# opi_link_X_standard.net
KiCad netlist of a schematic drawn in Altium Designer
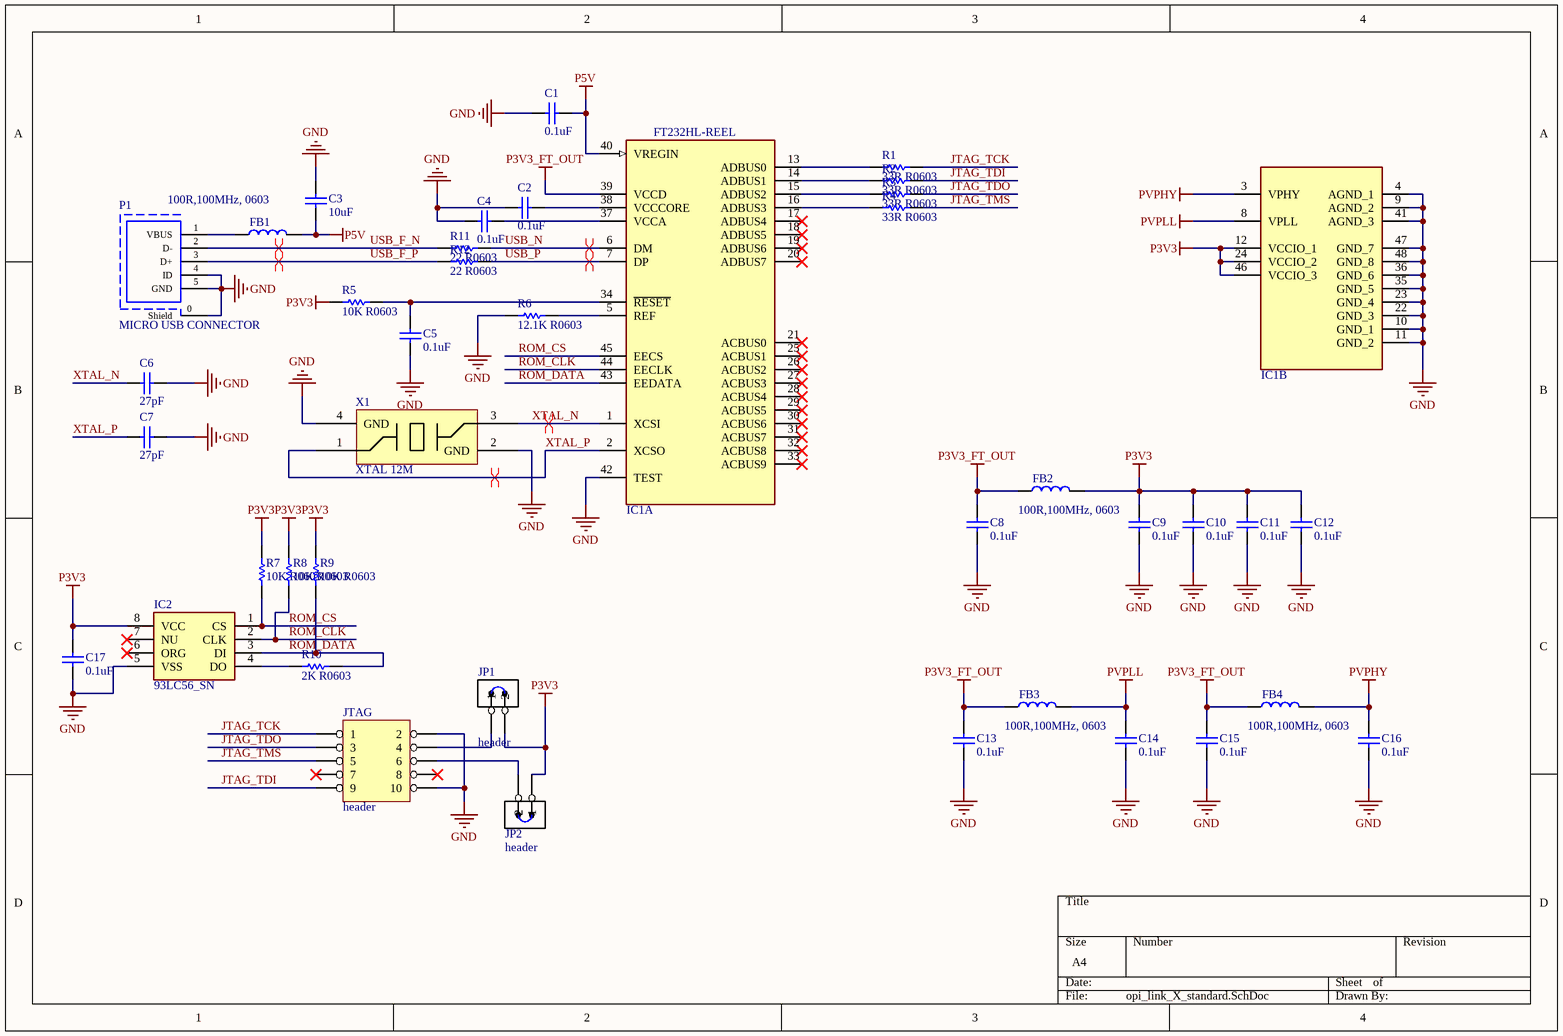
[diagram p0: opi_link_X_standard.SchDoc]

(export (version "E")
  (design (tool "Eeschema 10.0.6"))
  (components
    (comp (ref "C1")
      (value "0.1uF")
      (footprint "0603_C")
      (description "Capacitor")
      (fields (field (name "PUBLISHER") "Altium Limited"))
      (libsource (lib "My Footprint") (part "CAP"))
    )
    (comp (ref "C2")
      (value "0.1uF")
      (footprint "0603_C")
      (description "Capacitor")
      (fields (field (name "PUBLISHER") "Altium Limited"))
      (libsource (lib "My Footprint") (part "CAP"))
    )
    (comp (ref "C3")
      (value "10uF")
      (footprint "0805_c")
      (description "Capacitor")
      (fields (field (name "PUBLISHER") "Altium Limited"))
      (libsource (lib "My Footprint") (part "CAP"))
    )
    (comp (ref "C4")
      (value "0.1uF")
      (footprint "0603_C")
      (description "Capacitor")
      (fields (field (name "PUBLISHER") "Altium Limited"))
      (libsource (lib "My Footprint") (part "CAP"))
    )
    (comp (ref "C5")
      (value "0.1uF")
      (footprint "0603_C")
      (description "Capacitor")
      (fields (field (name "PUBLISHER") "Altium Limited"))
      (libsource (lib "My Footprint") (part "CAP"))
    )
    (comp (ref "C6")
      (value "27pF")
      (footprint "0603_C")
      (description "Capacitor")
      (fields (field (name "PUBLISHER") "Altium Limited"))
      (libsource (lib "My Footprint") (part "CAP"))
    )
    (comp (ref "C7")
      (value "27pF")
      (footprint "0603_C")
      (description "Capacitor")
      (fields (field (name "PUBLISHER") "Altium Limited"))
      (libsource (lib "My Footprint") (part "CAP"))
    )
    (comp (ref "C8")
      (value "0.1uF")
      (footprint "0603_C")
      (description "Capacitor")
      (fields (field (name "PUBLISHER") "Altium Limited"))
      (libsource (lib "My Footprint") (part "CAP"))
    )
    (comp (ref "C9")
      (value "0.1uF")
      (footprint "0603_C")
      (description "Capacitor")
      (fields (field (name "PUBLISHER") "Altium Limited"))
      (libsource (lib "My Footprint") (part "CAP"))
    )
    (comp (ref "C10")
      (value "0.1uF")
      (footprint "0603_C")
      (description "Capacitor")
      (fields (field (name "PUBLISHER") "Altium Limited"))
      (libsource (lib "My Footprint") (part "CAP"))
    )
    (comp (ref "C11")
      (value "0.1uF")
      (footprint "0603_C")
      (description "Capacitor")
      (fields (field (name "PUBLISHER") "Altium Limited"))
      (libsource (lib "My Footprint") (part "CAP"))
    )
    (comp (ref "C12")
      (value "0.1uF")
      (footprint "0603_C")
      (description "Capacitor")
      (fields (field (name "PUBLISHER") "Altium Limited"))
      (libsource (lib "My Footprint") (part "CAP"))
    )
    (comp (ref "C13")
      (value "0.1uF")
      (footprint "0603_C")
      (description "Capacitor")
      (fields (field (name "PUBLISHER") "Altium Limited"))
      (libsource (lib "My Footprint") (part "CAP"))
    )
    (comp (ref "C14")
      (value "0.1uF")
      (footprint "0603_C")
      (description "Capacitor")
      (fields (field (name "PUBLISHER") "Altium Limited"))
      (libsource (lib "My Footprint") (part "CAP"))
    )
    (comp (ref "C15")
      (value "0.1uF")
      (footprint "0603_C")
      (description "Capacitor")
      (fields (field (name "PUBLISHER") "Altium Limited"))
      (libsource (lib "My Footprint") (part "CAP"))
    )
    (comp (ref "C16")
      (value "0.1uF")
      (footprint "0603_C")
      (description "Capacitor")
      (fields (field (name "PUBLISHER") "Altium Limited"))
      (libsource (lib "My Footprint") (part "CAP"))
    )
    (comp (ref "C17")
      (value "0.1uF")
      (footprint "0603_C")
      (description "Capacitor")
      (fields (field (name "PUBLISHER") "Altium Limited"))
      (libsource (lib "My Footprint") (part "CAP"))
    )
    (comp (ref "FB1")
      (value "100R,100MHz, 0603")
      (footprint "0603")
      (description "磁珠")
      (libsource (lib "My Footprint") (part "FB"))
    )
    (comp (ref "FB2")
      (value "100R,100MHz, 0603")
      (footprint "0603")
      (description "磁珠")
      (libsource (lib "My Footprint") (part "FB"))
    )
    (comp (ref "FB3")
      (value "100R,100MHz, 0603")
      (footprint "0603")
      (description "磁珠")
      (libsource (lib "My Footprint") (part "FB"))
    )
    (comp (ref "FB4")
      (value "100R,100MHz, 0603")
      (footprint "0603")
      (description "磁珠")
      (libsource (lib "My Footprint") (part "FB"))
    )
    (comp (ref "IC1")
      (value "FT232HL-REEL")
      (footprint "LQFP48")
      (description "Integrated Circuit")
      (fields (field (name "MOUSER PART NUMBER") "895-FT232HL-REEL"))
      (libsource (lib "SamacSys") (part "FT232HL-REEL"))
    )
    (comp (ref "IC2")
      (value "93LC56_SN")
      (footprint "SamacSys:SOIC127P600X175-8N")
      (description "Integrated Circuit")
      (fields
        (field (name "MANUFACTURER_PART_NUMBER") "93LC56/SN")
        (field (name "MOUSER PART NUMBER") "579-93LC56SN")
      )
      (libsource (lib "SamacSys") (part "93LC56_SN"))
    )
    (comp (ref "JP1")
      (value "header")
      (footprint "jumper")
      (libsource (lib "My Footprint") (part "HEADER 2"))
    )
    (comp (ref "JP2") (value "header") (footprint "jumper") (libsource (lib "") (part "HEADER 2_1")))
    (comp (ref "JTAG")
      (value "header")
      (footprint "header2X5")
      (libsource (lib "My Footprint") (part "HEADER 5X2"))
    )
    (comp (ref "P1")
      (value "MICRO USB CONNECTOR")
      (footprint "USB_Micro_qian")
      (libsource (lib "My Footprint") (part "MICRO USB_in"))
    )
    (comp (ref "R1")
      (value "33R R0603")
      (footprint "0603_R")
      (description "Resistor")
      (fields (field (name "PUBLISHER") "Altium Limited"))
      (libsource (lib "My Footprint") (part "RES"))
    )
    (comp (ref "R2")
      (value "33R R0603")
      (footprint "0603_R")
      (description "Resistor")
      (fields (field (name "PUBLISHER") "Altium Limited"))
      (libsource (lib "My Footprint") (part "RES"))
    )
    (comp (ref "R3")
      (value "33R R0603")
      (footprint "0603_R")
      (description "Resistor")
      (fields (field (name "PUBLISHER") "Altium Limited"))
      (libsource (lib "My Footprint") (part "RES"))
    )
    (comp (ref "R4")
      (value "33R R0603")
      (footprint "0603_R")
      (description "Resistor")
      (fields (field (name "PUBLISHER") "Altium Limited"))
      (libsource (lib "My Footprint") (part "RES"))
    )
    (comp (ref "R5")
      (value "10K R0603")
      (footprint "0603_R")
      (description "Resistor")
      (fields (field (name "PUBLISHER") "Altium Limited"))
      (libsource (lib "My Footprint") (part "RES"))
    )
    (comp (ref "R6")
      (value "12.1K R0603")
      (footprint "0603_R")
      (description "Resistor")
      (fields (field (name "PUBLISHER") "Altium Limited"))
      (libsource (lib "My Footprint") (part "RES"))
    )
    (comp (ref "R7")
      (value "10K R0603")
      (footprint "0603_R")
      (description "Resistor")
      (fields (field (name "PUBLISHER") "Altium Limited"))
      (libsource (lib "My Footprint") (part "RES"))
    )
    (comp (ref "R8")
      (value "10K R0603")
      (footprint "0603_R")
      (description "Resistor")
      (fields (field (name "PUBLISHER") "Altium Limited"))
      (libsource (lib "My Footprint") (part "RES"))
    )
    (comp (ref "R9")
      (value "10K R0603")
      (footprint "0603_R")
      (description "Resistor")
      (fields (field (name "PUBLISHER") "Altium Limited"))
      (libsource (lib "My Footprint") (part "RES"))
    )
    (comp (ref "R10")
      (value "2K R0603")
      (footprint "0603_R")
      (description "Resistor")
      (fields (field (name "PUBLISHER") "Altium Limited"))
      (libsource (lib "My Footprint") (part "RES"))
    )
    (comp (ref "R11")
      (value "22 R0603")
      (footprint "0603_R")
      (description "Resistor")
      (fields (field (name "PUBLISHER") "Altium Limited"))
      (libsource (lib "My Footprint") (part "RES"))
    )
    (comp (ref "R12")
      (value "22 R0603")
      (footprint "0603_R")
      (description "Resistor")
      (fields (field (name "PUBLISHER") "Altium Limited"))
      (libsource (lib "My Footprint") (part "RES"))
    )
    (comp (ref "X1")
      (value "XTAL 12M")
      (footprint "OSC_KH3225_4P")
      (libsource (lib "My Footprint") (part "XTAL_SMT"))
    )
  )
  (nets
    (net (code "1") (name "/JTAG_TCK") (class "Default")
      (node (ref "JTAG") (pin "1") (pinfunction "1_1") (pintype "passive"))
      (node (ref "R1") (pin "2") (pinfunction "2_2") (pintype "passive"))
    )
    (net (code "2") (name "/JTAG_TDI") (class "Default")
      (node (ref "JTAG") (pin "9") (pinfunction "9_9") (pintype "passive"))
      (node (ref "R2") (pin "2") (pinfunction "2_2") (pintype "passive"))
    )
    (net (code "3") (name "/JTAG_TDO") (class "Default")
      (node (ref "JTAG") (pin "3") (pinfunction "3_3") (pintype "passive"))
      (node (ref "R3") (pin "2") (pinfunction "2_2") (pintype "passive"))
    )
    (net (code "4") (name "/JTAG_TMS") (class "Default")
      (node (ref "JTAG") (pin "5") (pinfunction "5_5") (pintype "passive"))
      (node (ref "R4") (pin "2") (pinfunction "2_2") (pintype "passive"))
    )
    (net (code "5") (name "/ROM_CLK") (class "Default")
      (node (ref "IC1") (pin "44") (pinfunction "EECLK_44") (pintype "passive"))
      (node (ref "IC2") (pin "2") (pinfunction "CLK_2") (pintype "passive"))
      (node (ref "R8") (pin "1") (pinfunction "1_1") (pintype "passive"))
    )
    (net (code "6") (name "/ROM_CS") (class "Default")
      (node (ref "IC1") (pin "45") (pinfunction "EECS_45") (pintype "passive"))
      (node (ref "IC2") (pin "1") (pinfunction "CS_1") (pintype "passive"))
      (node (ref "R7") (pin "1") (pinfunction "1_1") (pintype "passive"))
    )
    (net (code "7") (name "/ROM_DATA") (class "Default")
      (node (ref "IC1") (pin "43") (pinfunction "EEDATA_43") (pintype "passive"))
      (node (ref "IC2") (pin "3") (pinfunction "DI_3") (pintype "passive"))
      (node (ref "R10") (pin "2") (pinfunction "2_2") (pintype "passive"))
      (node (ref "R9") (pin "1") (pinfunction "1_1") (pintype "passive"))
    )
    (net (code "8") (name "/USB_F_N") (class "Default")
      (node (ref "P1") (pin "2") (pinfunction "D-_2") (pintype "passive"))
      (node (ref "R11") (pin "1") (pinfunction "1_1") (pintype "passive"))
    )
    (net (code "9") (name "/USB_F_P") (class "Default")
      (node (ref "P1") (pin "3") (pinfunction "D+_3") (pintype "passive"))
      (node (ref "R12") (pin "1") (pinfunction "1_1") (pintype "passive"))
    )
    (net (code "10") (name "/USB_N") (class "Default")
      (node (ref "IC1") (pin "6") (pinfunction "DM_6") (pintype "passive"))
      (node (ref "R11") (pin "2") (pinfunction "2_2") (pintype "passive"))
    )
    (net (code "11") (name "/USB_P") (class "Default")
      (node (ref "IC1") (pin "7") (pinfunction "DP_7") (pintype "passive"))
      (node (ref "R12") (pin "2") (pinfunction "2_2") (pintype "passive"))
    )
    (net (code "12") (name "/XTAL_N") (class "Default")
      (node (ref "C6") (pin "1") (pinfunction "1_1") (pintype "passive"))
      (node (ref "IC1") (pin "1") (pinfunction "XCSI_1") (pintype "passive"))
      (node (ref "X1") (pin "3") (pinfunction "OSC2_3") (pintype "passive"))
    )
    (net (code "13") (name "/XTAL_P") (class "Default")
      (node (ref "C7") (pin "1") (pinfunction "1_1") (pintype "passive"))
      (node (ref "IC1") (pin "2") (pinfunction "XCSO_2") (pintype "passive"))
      (node (ref "X1") (pin "1") (pinfunction "OSC1_1") (pintype "passive"))
    )
    (net (code "14") (name "GND") (class "Default")
      (node (ref "C1") (pin "1") (pinfunction "1_1") (pintype "passive"))
      (node (ref "C10") (pin "1") (pinfunction "1_1") (pintype "passive"))
      (node (ref "C11") (pin "1") (pinfunction "1_1") (pintype "passive"))
      (node (ref "C12") (pin "1") (pinfunction "1_1") (pintype "passive"))
      (node (ref "C13") (pin "1") (pinfunction "1_1") (pintype "passive"))
      (node (ref "C14") (pin "1") (pinfunction "1_1") (pintype "passive"))
      (node (ref "C15") (pin "1") (pinfunction "1_1") (pintype "passive"))
      (node (ref "C16") (pin "1") (pinfunction "1_1") (pintype "passive"))
      (node (ref "C17") (pin "1") (pinfunction "1_1") (pintype "passive"))
      (node (ref "C2") (pin "2") (pinfunction "2_2") (pintype "passive"))
      (node (ref "C3") (pin "2") (pinfunction "2_2") (pintype "passive"))
      (node (ref "C4") (pin "2") (pinfunction "2_2") (pintype "passive"))
      (node (ref "C5") (pin "2") (pinfunction "2_2") (pintype "passive"))
      (node (ref "C6") (pin "2") (pinfunction "2_2") (pintype "passive"))
      (node (ref "C7") (pin "2") (pinfunction "2_2") (pintype "passive"))
      (node (ref "C8") (pin "1") (pinfunction "1_1") (pintype "passive"))
      (node (ref "C9") (pin "1") (pinfunction "1_1") (pintype "passive"))
      (node (ref "IC1") (pin "10") (pinfunction "GND_1_10") (pintype "power_in"))
      (node (ref "IC1") (pin "11") (pinfunction "GND_2_11") (pintype "power_in"))
      (node (ref "IC1") (pin "22") (pinfunction "GND_3_22") (pintype "power_in"))
      (node (ref "IC1") (pin "23") (pinfunction "GND_4_23") (pintype "power_in"))
      (node (ref "IC1") (pin "35") (pinfunction "GND_5_35") (pintype "power_in"))
      (node (ref "IC1") (pin "36") (pinfunction "GND_6_36") (pintype "power_in"))
      (node (ref "IC1") (pin "4") (pinfunction "AGND_1_4") (pintype "power_in"))
      (node (ref "IC1") (pin "41") (pinfunction "AGND_3_41") (pintype "power_in"))
      (node (ref "IC1") (pin "42") (pinfunction "TEST_42") (pintype "passive"))
      (node (ref "IC1") (pin "47") (pinfunction "GND_7_47") (pintype "power_in"))
      (node (ref "IC1") (pin "48") (pinfunction "GND_8_48") (pintype "power_in"))
      (node (ref "IC1") (pin "9") (pinfunction "AGND_2_9") (pintype "power_in"))
      (node (ref "IC2") (pin "5") (pinfunction "VSS_5") (pintype "passive"))
      (node (ref "JTAG") (pin "10") (pinfunction "10_10") (pintype "passive"))
      (node (ref "JTAG") (pin "2") (pinfunction "2_2") (pintype "passive"))
      (node (ref "P1") (pin "0") (pinfunction "Shield_0") (pintype "passive"))
      (node (ref "P1") (pin "4") (pinfunction "ID_4") (pintype "passive"))
      (node (ref "P1") (pin "5") (pinfunction "GND_5") (pintype "passive"))
      (node (ref "R6") (pin "1") (pinfunction "1_1") (pintype "passive"))
      (node (ref "X1") (pin "2") (pinfunction "GND_2") (pintype "passive"))
      (node (ref "X1") (pin "4") (pinfunction "GND_4") (pintype "passive"))
    )
    (net (code "15") (name "Net-(IC1A-ADBUS0)") (class "Default")
      (node (ref "IC1") (pin "13") (pinfunction "ADBUS0_13") (pintype "passive"))
      (node (ref "R1") (pin "1") (pinfunction "1_1") (pintype "passive"))
    )
    (net (code "16") (name "Net-(IC1A-ADBUS1)") (class "Default")
      (node (ref "IC1") (pin "14") (pinfunction "ADBUS1_14") (pintype "passive"))
      (node (ref "R2") (pin "1") (pinfunction "1_1") (pintype "passive"))
    )
    (net (code "17") (name "Net-(IC1A-ADBUS2)") (class "Default")
      (node (ref "IC1") (pin "15") (pinfunction "ADBUS2_15") (pintype "passive"))
      (node (ref "R3") (pin "1") (pinfunction "1_1") (pintype "passive"))
    )
    (net (code "18") (name "Net-(IC1A-ADBUS3)") (class "Default")
      (node (ref "IC1") (pin "16") (pinfunction "ADBUS3_16") (pintype "passive"))
      (node (ref "R4") (pin "1") (pinfunction "1_1") (pintype "passive"))
    )
    (net (code "19") (name "Net-(IC1A-REF)") (class "Default")
      (node (ref "IC1") (pin "5") (pinfunction "REF_5") (pintype "passive"))
      (node (ref "R6") (pin "2") (pinfunction "2_2") (pintype "passive"))
    )
    (net (code "20") (name "Net-(IC1A-VCCA)") (class "Default")
      (node (ref "C4") (pin "1") (pinfunction "1_1") (pintype "passive"))
      (node (ref "IC1") (pin "37") (pinfunction "VCCA_37") (pintype "power_in"))
    )
    (net (code "21") (name "Net-(IC1A-VCCCORE)") (class "Default")
      (node (ref "C2") (pin "1") (pinfunction "1_1") (pintype "passive"))
      (node (ref "IC1") (pin "38") (pinfunction "VCCCORE_38") (pintype "power_in"))
    )
    (net (code "22") (name "Net-(IC1A-~{RESET})") (class "Default")
      (node (ref "C5") (pin "1") (pinfunction "1_1") (pintype "passive"))
      (node (ref "IC1") (pin "34") (pinfunction "~{RESET}_34") (pintype "passive"))
      (node (ref "R5") (pin "2") (pinfunction "2_2") (pintype "passive"))
    )
    (net (code "23") (name "Net-(IC2-DO)") (class "Default")
      (node (ref "IC2") (pin "4") (pinfunction "DO_4") (pintype "passive"))
      (node (ref "R10") (pin "1") (pinfunction "1_1") (pintype "passive"))
    )
    (net (code "24") (name "Net-(JP1-Pad1)") (class "Default")
      (node (ref "JP1") (pin "1") (pinfunction "1_1") (pintype "passive"))
      (node (ref "JTAG") (pin "4") (pinfunction "4_4") (pintype "passive"))
    )
    (net (code "25") (name "Net-(JP2-Pad2)") (class "Default")
      (node (ref "JP2") (pin "2") (pinfunction "2_2") (pintype "passive"))
      (node (ref "JTAG") (pin "6") (pinfunction "6_6") (pintype "passive"))
    )
    (net (code "26") (name "Net-(P1-VBUS)") (class "Default")
      (node (ref "FB1") (pin "1") (pinfunction "1_1") (pintype "passive"))
      (node (ref "P1") (pin "1") (pinfunction "VBUS_1") (pintype "passive"))
    )
    (net (code "27") (name "P3V3") (class "Default")
      (node (ref "C10") (pin "2") (pinfunction "2_2") (pintype "passive"))
      (node (ref "C11") (pin "2") (pinfunction "2_2") (pintype "passive"))
      (node (ref "C12") (pin "2") (pinfunction "2_2") (pintype "passive"))
      (node (ref "C17") (pin "2") (pinfunction "2_2") (pintype "passive"))
      (node (ref "C9") (pin "2") (pinfunction "2_2") (pintype "passive"))
      (node (ref "FB2") (pin "2") (pinfunction "2_2") (pintype "passive"))
      (node (ref "IC1") (pin "12") (pinfunction "VCCIO_1_12") (pintype "power_in"))
      (node (ref "IC1") (pin "24") (pinfunction "VCCIO_2_24") (pintype "power_in"))
      (node (ref "IC1") (pin "46") (pinfunction "VCCIO_3_46") (pintype "power_in"))
      (node (ref "IC2") (pin "8") (pinfunction "VCC_8") (pintype "passive"))
      (node (ref "JP1") (pin "2") (pinfunction "2_2") (pintype "passive"))
      (node (ref "JP2") (pin "1") (pinfunction "1_1") (pintype "passive"))
      (node (ref "R5") (pin "1") (pinfunction "1_1") (pintype "passive"))
      (node (ref "R7") (pin "2") (pinfunction "2_2") (pintype "passive"))
      (node (ref "R8") (pin "2") (pinfunction "2_2") (pintype "passive"))
      (node (ref "R9") (pin "2") (pinfunction "2_2") (pintype "passive"))
    )
    (net (code "28") (name "P3V3_FT_OUT") (class "Default")
      (node (ref "C13") (pin "2") (pinfunction "2_2") (pintype "passive"))
      (node (ref "C15") (pin "2") (pinfunction "2_2") (pintype "passive"))
      (node (ref "C8") (pin "2") (pinfunction "2_2") (pintype "passive"))
      (node (ref "FB2") (pin "1") (pinfunction "1_1") (pintype "passive"))
      (node (ref "FB3") (pin "1") (pinfunction "1_1") (pintype "passive"))
      (node (ref "FB4") (pin "1") (pinfunction "1_1") (pintype "passive"))
      (node (ref "IC1") (pin "39") (pinfunction "VCCD_39") (pintype "power_in"))
    )
    (net (code "29") (name "P5V") (class "Default")
      (node (ref "C1") (pin "2") (pinfunction "2_2") (pintype "passive"))
      (node (ref "C3") (pin "1") (pinfunction "1_1") (pintype "passive"))
      (node (ref "FB1") (pin "2") (pinfunction "2_2") (pintype "passive"))
      (node (ref "IC1") (pin "40") (pinfunction "VREGIN_40") (pintype "input"))
    )
    (net (code "30") (name "PVPHY") (class "Default")
      (node (ref "C16") (pin "2") (pinfunction "2_2") (pintype "passive"))
      (node (ref "FB4") (pin "2") (pinfunction "2_2") (pintype "passive"))
      (node (ref "IC1") (pin "3") (pinfunction "VPHY_3") (pintype "passive"))
    )
    (net (code "31") (name "PVPLL") (class "Default")
      (node (ref "C14") (pin "2") (pinfunction "2_2") (pintype "passive"))
      (node (ref "FB3") (pin "2") (pinfunction "2_2") (pintype "passive"))
      (node (ref "IC1") (pin "8") (pinfunction "VPLL_8") (pintype "passive"))
    )
    (net (code "32") (name "unconnected-(IC1A-ACBUS0-Pad21)") (class "Default")
      (node (ref "IC1") (pin "21") (pinfunction "ACBUS0_21") (pintype "passive+no_connect"))
    )
    (net (code "33") (name "unconnected-(IC1A-ACBUS1-Pad25)") (class "Default")
      (node (ref "IC1") (pin "25") (pinfunction "ACBUS1_25") (pintype "passive+no_connect"))
    )
    (net (code "34") (name "unconnected-(IC1A-ACBUS2-Pad26)") (class "Default")
      (node (ref "IC1") (pin "26") (pinfunction "ACBUS2_26") (pintype "passive+no_connect"))
    )
    (net (code "35") (name "unconnected-(IC1A-ACBUS3-Pad27)") (class "Default")
      (node (ref "IC1") (pin "27") (pinfunction "ACBUS3_27") (pintype "passive+no_connect"))
    )
    (net (code "36") (name "unconnected-(IC1A-ACBUS4-Pad28)") (class "Default")
      (node (ref "IC1") (pin "28") (pinfunction "ACBUS4_28") (pintype "passive+no_connect"))
    )
    (net (code "37") (name "unconnected-(IC1A-ACBUS5-Pad29)") (class "Default")
      (node (ref "IC1") (pin "29") (pinfunction "ACBUS5_29") (pintype "passive+no_connect"))
    )
    (net (code "38") (name "unconnected-(IC1A-ACBUS6-Pad30)") (class "Default")
      (node (ref "IC1") (pin "30") (pinfunction "ACBUS6_30") (pintype "passive+no_connect"))
    )
    (net (code "39") (name "unconnected-(IC1A-ACBUS7-Pad31)") (class "Default")
      (node (ref "IC1") (pin "31") (pinfunction "ACBUS7_31") (pintype "passive+no_connect"))
    )
    (net (code "40") (name "unconnected-(IC1A-ACBUS8-Pad32)") (class "Default")
      (node (ref "IC1") (pin "32") (pinfunction "ACBUS8_32") (pintype "passive+no_connect"))
    )
    (net (code "41") (name "unconnected-(IC1A-ACBUS9-Pad33)") (class "Default")
      (node (ref "IC1") (pin "33") (pinfunction "ACBUS9_33") (pintype "passive+no_connect"))
    )
    (net (code "42") (name "unconnected-(IC1A-ADBUS4-Pad17)") (class "Default")
      (node (ref "IC1") (pin "17") (pinfunction "ADBUS4_17") (pintype "passive+no_connect"))
    )
    (net (code "43") (name "unconnected-(IC1A-ADBUS5-Pad18)") (class "Default")
      (node (ref "IC1") (pin "18") (pinfunction "ADBUS5_18") (pintype "passive+no_connect"))
    )
    (net (code "44") (name "unconnected-(IC1A-ADBUS6-Pad19)") (class "Default")
      (node (ref "IC1") (pin "19") (pinfunction "ADBUS6_19") (pintype "passive+no_connect"))
    )
    (net (code "45") (name "unconnected-(IC1A-ADBUS7-Pad20)") (class "Default")
      (node (ref "IC1") (pin "20") (pinfunction "ADBUS7_20") (pintype "passive+no_connect"))
    )
    (net (code "46") (name "unconnected-(IC2-NU-Pad7)") (class "Default")
      (node (ref "IC2") (pin "7") (pinfunction "NU_7") (pintype "passive+no_connect"))
    )
    (net (code "47") (name "unconnected-(IC2-ORG-Pad6)") (class "Default")
      (node (ref "IC2") (pin "6") (pinfunction "ORG_6") (pintype "passive+no_connect"))
    )
    (net (code "48") (name "unconnected-(JTAG-Pad7)") (class "Default")
      (node (ref "JTAG") (pin "7") (pinfunction "7_7") (pintype "passive+no_connect"))
    )
    (net (code "49") (name "unconnected-(JTAG-Pad8)") (class "Default")
      (node (ref "JTAG") (pin "8") (pinfunction "8_8") (pintype "passive+no_connect"))
    )
  )
)
